# BFmsp430.net
KiCad netlist of a schematic drawn in Altium Designer
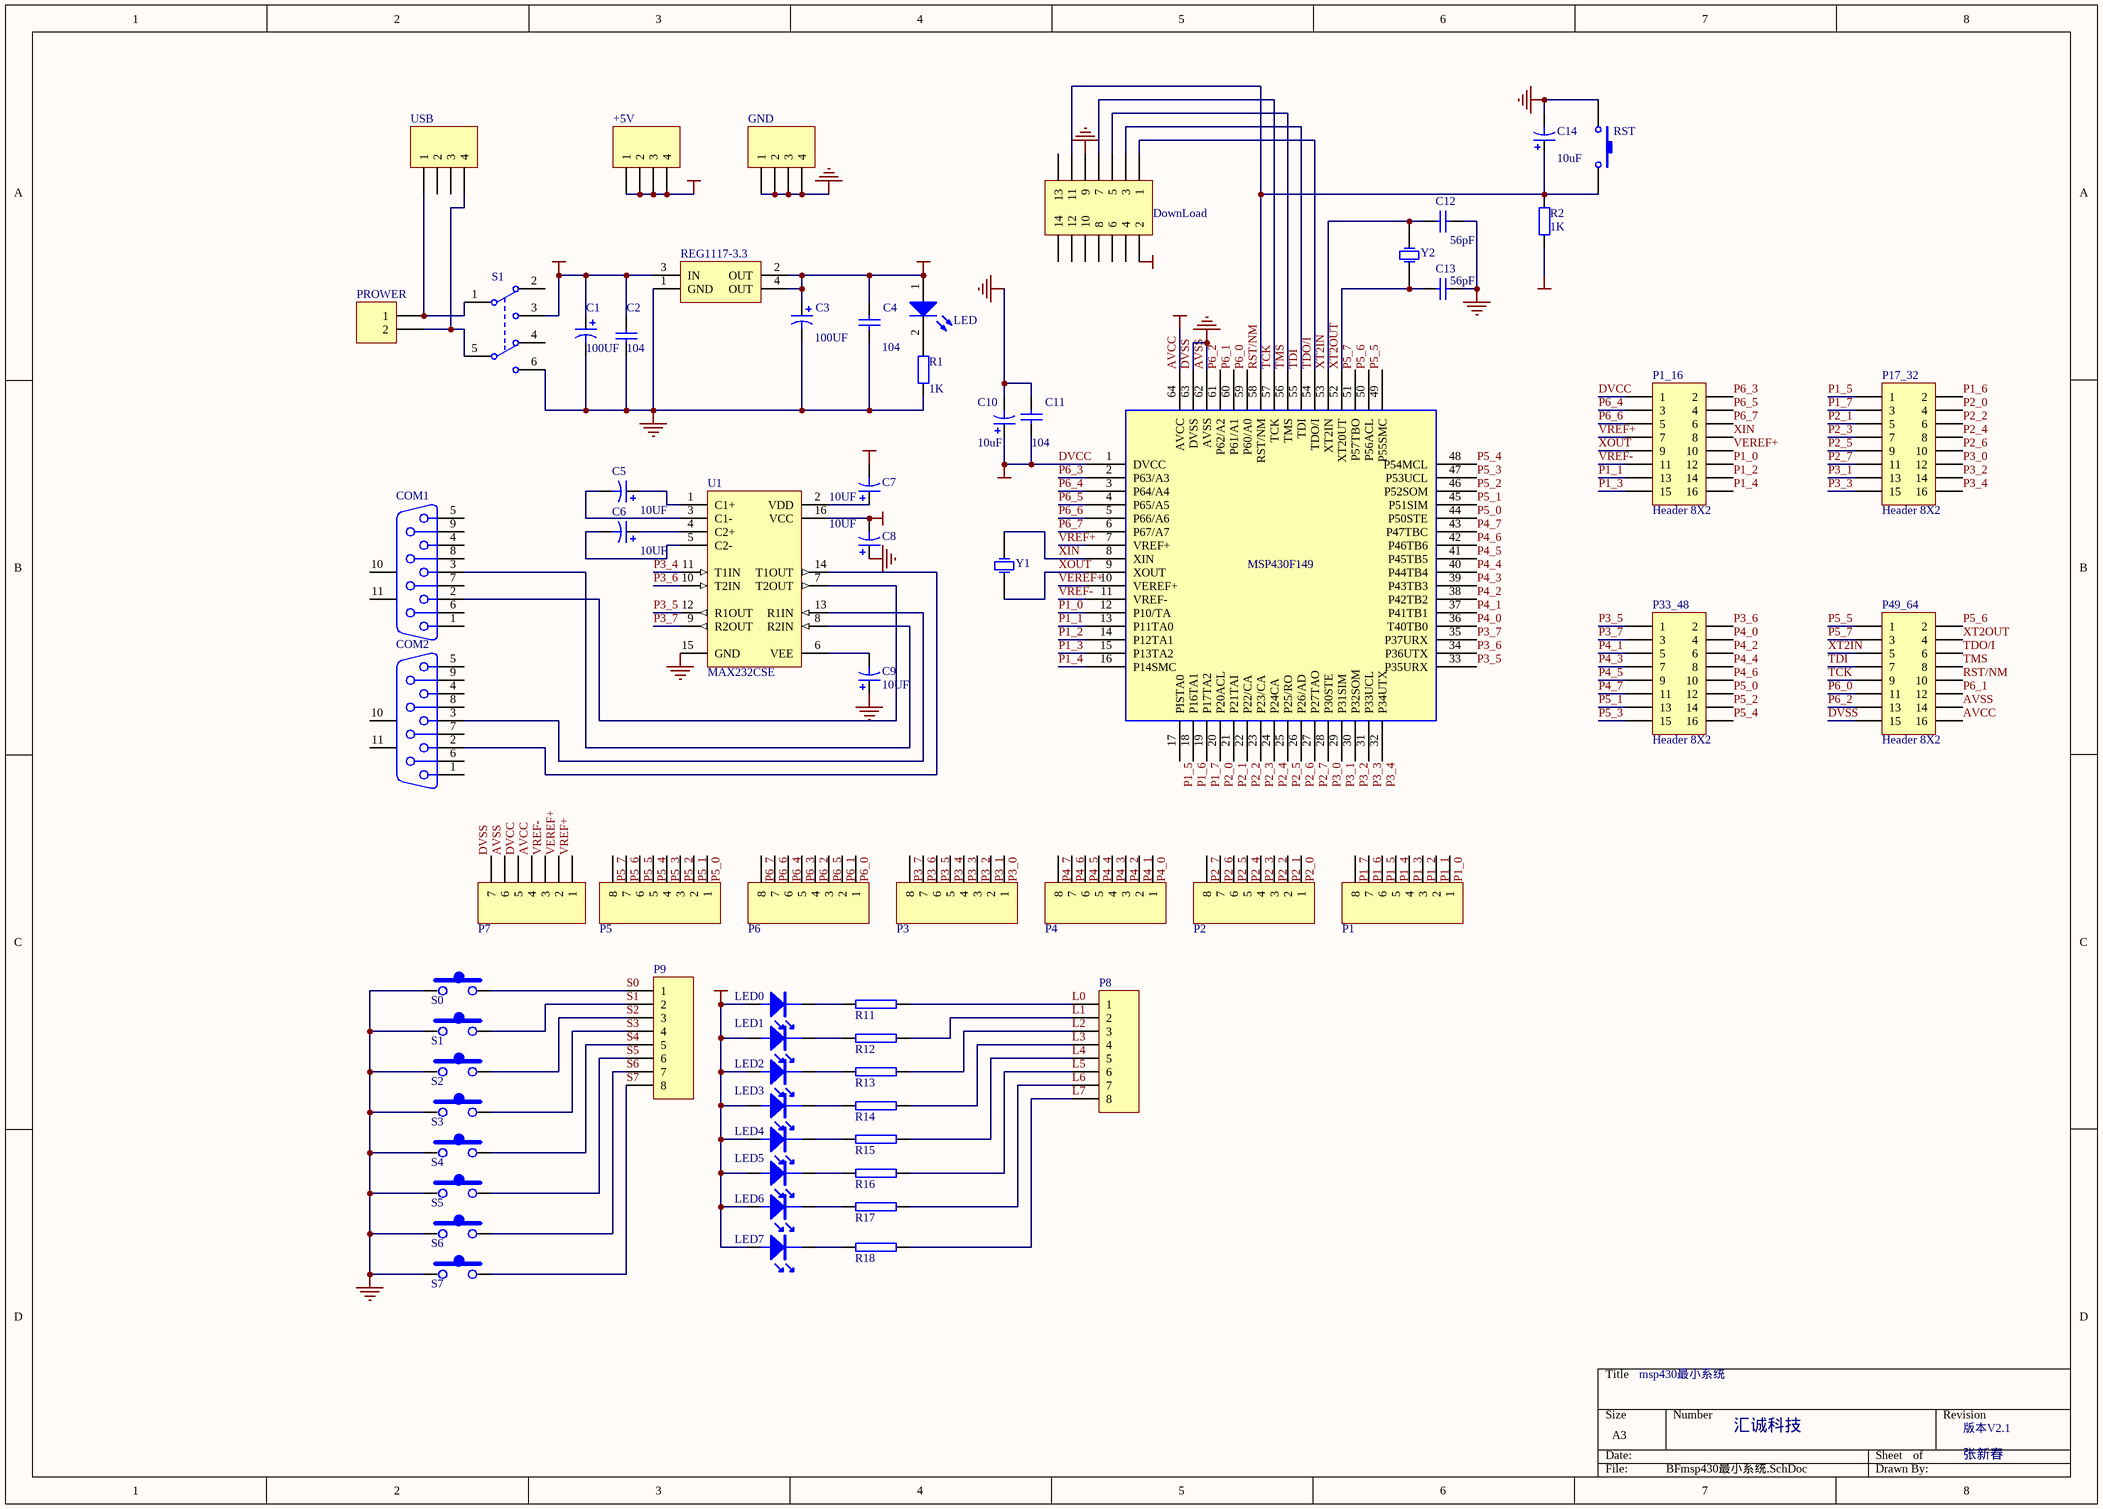
[diagram p0: BFmsp430最小系统.SchDoc]

(export (version "E")
  (design (tool "Eeschema 10.0.6"))
  (components
    (comp (ref "+5V")
      (value "Header 4")
      (footprint "HDR1X4")
      (description "Header, 4-Pin")
      (fields (field (name "PUBLISHER") "Altium Limited"))
      (libsource (lib "Miscellaneous Connectors") (part "Header 4"))
    )
    (comp (ref "1") (value "S0") (footprint "an-6*6") (libsource (lib "OldCow1 (1)") (part "KEY")))
    (comp (ref "2") (value "S1") (footprint "an-6*6") (libsource (lib "OldCow1 (1)") (part "KEY")))
    (comp (ref "3") (value "S2") (footprint "an-6*6") (libsource (lib "OldCow1 (1)") (part "KEY")))
    (comp (ref "4") (value "S3") (footprint "an-6*6") (libsource (lib "OldCow1 (1)") (part "KEY")))
    (comp (ref "5") (value "S4") (footprint "an-6*6") (libsource (lib "OldCow1 (1)") (part "KEY")))
    (comp (ref "6") (value "S5") (footprint "an-6*6") (libsource (lib "OldCow1 (1)") (part "KEY")))
    (comp (ref "7") (value "S6") (footprint "an-6*6") (libsource (lib "OldCow1 (1)") (part "KEY")))
    (comp (ref "8") (value "S7") (footprint "an-6*6") (libsource (lib "OldCow1 (1)") (part "KEY")))
    (comp (ref "C1")
      (value "100UF")
      (footprint "C-DJ-6")
      (description "Polarized Capacitor (Radial)")
      (fields (field (name "Comment") "Cap Pol1") (field (name "PUBLISHER") "Altium Limited"))
      (libsource (lib "Miscellaneous Devices") (part "Cap Pol1"))
    )
    (comp (ref "C2")
      (value "104")
      (footprint "CPDR")
      (description "Capacitor (Semiconductor SIM Model)")
      (fields (field (name "Comment") "Cap Semi") (field (name "PUBLISHER") "Altium Limited"))
      (libsource (lib "Miscellaneous Devices") (part "Cap Semi"))
    )
    (comp (ref "C3")
      (value "100UF")
      (footprint "C-DJ-4")
      (description "Polarized Capacitor (Radial)")
      (fields (field (name "Comment") "Cap Pol1") (field (name "PUBLISHER") "Altium Limited"))
      (libsource (lib "Miscellaneous Devices") (part "Cap Pol1"))
    )
    (comp (ref "C4")
      (value "104")
      (footprint "CPDR")
      (description "Capacitor (Semiconductor SIM Model)")
      (fields (field (name "Comment") "Cap Semi") (field (name "PUBLISHER") "Altium Limited"))
      (libsource (lib "Miscellaneous Devices") (part "Cap Semi"))
    )
    (comp (ref "C5")
      (value "10UF")
      (footprint "C-DJ-4")
      (description "Polarized Capacitor (Radial)")
      (fields (field (name "Comment") "Cap Pol1") (field (name "PUBLISHER") "Altium Limited"))
      (libsource (lib "Miscellaneous Devices") (part "Cap Pol1"))
    )
    (comp (ref "C6")
      (value "10UF")
      (footprint "C-DJ-4")
      (description "Polarized Capacitor (Radial)")
      (fields (field (name "Comment") "Cap Pol1") (field (name "PUBLISHER") "Altium Limited"))
      (libsource (lib "Miscellaneous Devices") (part "Cap Pol1"))
    )
    (comp (ref "C7")
      (value "10UF")
      (footprint "C-DJ-4")
      (description "Polarized Capacitor (Radial)")
      (fields (field (name "Comment") "Cap Pol1") (field (name "PUBLISHER") "Altium Limited"))
      (libsource (lib "Miscellaneous Devices") (part "Cap Pol1"))
    )
    (comp (ref "C8")
      (value "10UF")
      (footprint "C-DJ-4")
      (description "Polarized Capacitor (Radial)")
      (fields (field (name "Comment") "Cap Pol1") (field (name "PUBLISHER") "Altium Limited"))
      (libsource (lib "Miscellaneous Devices") (part "Cap Pol1"))
    )
    (comp (ref "C9")
      (value "10UF")
      (footprint "C-DJ-4")
      (description "Polarized Capacitor (Radial)")
      (fields (field (name "Comment") "Cap Pol1") (field (name "PUBLISHER") "Altium Limited"))
      (libsource (lib "Miscellaneous Devices") (part "Cap Pol1"))
    )
    (comp (ref "C10")
      (value "10uF")
      (footprint "C-DJ-4")
      (description "Polarized Capacitor (Radial)")
      (fields (field (name "Comment") "Cap Pol1") (field (name "PUBLISHER") "Altium Limited"))
      (libsource (lib "Miscellaneous Devices") (part "Cap Pol1"))
    )
    (comp (ref "C11")
      (value "104")
      (footprint "CPDR")
      (description "Capacitor (Semiconductor SIM Model)")
      (fields (field (name "Comment") "Cap Semi") (field (name "PUBLISHER") "Altium Limited"))
      (libsource (lib "Miscellaneous Devices") (part "Cap Semi"))
    )
    (comp (ref "C12")
      (value "56pF")
      (footprint "CPDR")
      (description "瓷片电容")
      (fields (field (name "Comment") "CPDR") (field (name "PUBLISHER") "Altium Limited"))
      (libsource (lib "zxcourhc") (part "CPDR"))
    )
    (comp (ref "C13")
      (value "56pF")
      (footprint "CPDR")
      (description "瓷片电容")
      (fields (field (name "Comment") "CPDR") (field (name "PUBLISHER") "Altium Limited"))
      (libsource (lib "zxcourhc") (part "CPDR"))
    )
    (comp (ref "C14")
      (value "10uF")
      (footprint "C-DJ-4")
      (description "Polarized Capacitor (Radial)")
      (fields (field (name "Comment") "Cap Pol1") (field (name "PUBLISHER") "Altium Limited"))
      (libsource (lib "Miscellaneous Devices") (part "Cap Pol1"))
    )
    (comp (ref "COM1")
      (value "D Connector 9")
      (footprint "zxcourhc:COM-9")
      (description "Receptacle Assembly, 9 Position, Right Angle")
      (fields (field (name "PUBLISHER") "Altium Limited"))
      (libsource (lib "Miscellaneous Connectors") (part "D Connector 9"))
    )
    (comp (ref "COM2")
      (value "D Connector 9")
      (footprint "zxcourhc:COM-9")
      (description "Receptacle Assembly, 9 Position, Right Angle")
      (fields (field (name "PUBLISHER") "Altium Limited"))
      (libsource (lib "Miscellaneous Connectors") (part "D Connector 9"))
    )
    (comp (ref "DownLoad")
      (value "Header 7X2")
      (footprint "HDR-2X7")
      (description "Header, 7-Pin, Dual row")
      (fields (field (name "PUBLISHER") "Altium Limited"))
      (libsource (lib "Miscellaneous Connectors") (part "Header 7X2"))
    )
    (comp (ref "DS1")
      (value "LED")
      (footprint "LED")
      (description "发光二极管")
      (fields (field (name "PUBLISHER") "Altium Limited"))
      (libsource (lib "zxcourhc") (part "LED"))
    )
    (comp (ref "GND")
      (value "Header 4")
      (footprint "HDR1X4")
      (description "Header, 4-Pin")
      (fields (field (name "PUBLISHER") "Altium Limited"))
      (libsource (lib "Miscellaneous Connectors") (part "Header 4"))
    )
    (comp (ref "LED0") (value "LED") (footprint "TP-0805-D") (libsource (lib "OldCow1 (1)") (part "LED")))
    (comp (ref "LED1") (value "LED") (footprint "TP-0805-D") (libsource (lib "OldCow1 (1)") (part "LED")))
    (comp (ref "LED2") (value "LED") (footprint "TP-0805-D") (libsource (lib "OldCow1 (1)") (part "LED")))
    (comp (ref "LED3") (value "LED") (footprint "TP-0805-D") (libsource (lib "OldCow1 (1)") (part "LED")))
    (comp (ref "LED4") (value "LED") (footprint "TP-0805-D") (libsource (lib "OldCow1 (1)") (part "LED")))
    (comp (ref "LED5") (value "LED") (footprint "TP-0805-D") (libsource (lib "OldCow1 (1)") (part "LED")))
    (comp (ref "LED6") (value "LED") (footprint "TP-0805-D") (libsource (lib "OldCow1 (1)") (part "LED")))
    (comp (ref "LED7") (value "LED") (footprint "TP-0805-D") (libsource (lib "OldCow1 (1)") (part "LED")))
    (comp (ref "MSP430F149")
      (value "MSP430F149")
      (footprint "MPS430149")
      (libsource (lib "MyInt_Lib") (part "MSP430F133"))
    )
    (comp (ref "P1")
      (value "Header 8")
      (footprint "zxcourhc:HDR-8")
      (description "Header, 8-Pin")
      (fields (field (name "PUBLISHER") "Altium Limited"))
      (libsource (lib "Miscellaneous Connectors") (part "Header 8"))
    )
    (comp (ref "P1_16")
      (value "Header 8X2")
      (footprint "HDR2X8")
      (description "Header, 8-Pin, Dual row")
      (fields (field (name "PUBLISHER") "Altium Limited"))
      (libsource (lib "Miscellaneous Connectors") (part "Header 8X2"))
    )
    (comp (ref "P2")
      (value "Header 8")
      (footprint "zxcourhc:HD-8")
      (description "Header, 8-Pin")
      (fields (field (name "PUBLISHER") "Altium Limited"))
      (libsource (lib "Miscellaneous Connectors") (part "Header 8"))
    )
    (comp (ref "P3")
      (value "Header 8")
      (footprint "zxcourhc:HD-8")
      (description "Header, 8-Pin")
      (fields (field (name "PUBLISHER") "Altium Limited"))
      (libsource (lib "Miscellaneous Connectors") (part "Header 8"))
    )
    (comp (ref "P4")
      (value "Header 8")
      (footprint "zxcourhc:HD-8")
      (description "Header, 8-Pin")
      (fields (field (name "PUBLISHER") "Altium Limited"))
      (libsource (lib "Miscellaneous Connectors") (part "Header 8"))
    )
    (comp (ref "P5")
      (value "Header 8")
      (footprint "zxcourhc:HD-8")
      (description "Header, 8-Pin")
      (fields (field (name "PUBLISHER") "Altium Limited"))
      (libsource (lib "Miscellaneous Connectors") (part "Header 8"))
    )
    (comp (ref "P6")
      (value "Header 8")
      (footprint "zxcourhc:HD-8")
      (description "Header, 8-Pin")
      (fields (field (name "PUBLISHER") "Altium Limited"))
      (libsource (lib "Miscellaneous Connectors") (part "Header 8"))
    )
    (comp (ref "P7")
      (value "Header 7")
      (footprint "HDR1X7")
      (description "Header, 7-Pin")
      (fields (field (name "PUBLISHER") "Altium Limited"))
      (libsource (lib "Miscellaneous Connectors") (part "Header 7"))
    )
    (comp (ref "P8")
      (value "PZ_8")
      (footprint "HDR-8")
      (description "排针——8")
      (fields (field (name "PUBLISHER") "Altium Limited"))
      (libsource (lib "zxcourhc") (part "PZ_8"))
    )
    (comp (ref "P9")
      (value "PZ_8")
      (footprint "HDR-8")
      (description "排针——8")
      (fields (field (name "PUBLISHER") "Altium Limited"))
      (libsource (lib "zxcourhc") (part "PZ_8"))
    )
    (comp (ref "P17_32")
      (value "Header 8X2")
      (footprint "HDR2X8")
      (description "Header, 8-Pin, Dual row")
      (fields (field (name "PUBLISHER") "Altium Limited"))
      (libsource (lib "Miscellaneous Connectors") (part "Header 8X2"))
    )
    (comp (ref "P33_48")
      (value "Header 8X2")
      (footprint "HDR2X8")
      (description "Header, 8-Pin, Dual row")
      (fields (field (name "PUBLISHER") "Altium Limited"))
      (libsource (lib "Miscellaneous Connectors") (part "Header 8X2"))
    )
    (comp (ref "P49_64")
      (value "Header 8X2")
      (footprint "HDR2X8")
      (description "Header, 8-Pin, Dual row")
      (fields (field (name "PUBLISHER") "Altium Limited"))
      (libsource (lib "Miscellaneous Connectors") (part "Header 8X2"))
    )
    (comp (ref "PROWER")
      (value "PZ_2")
      (footprint "zxcourhc:JK128_2")
      (description "排针——2")
      (fields (field (name "PUBLISHER") "Altium Limited"))
      (libsource (lib "zxcourhc") (part "PZ_2"))
    )
    (comp (ref "R1")
      (value "1K")
      (footprint "TP-0805-R")
      (description "电阻")
      (fields (field (name "Comment") "Res") (field (name "PUBLISHER") "Altium Limited"))
      (libsource (lib "zxcourhc") (part "Res"))
    )
    (comp (ref "R2")
      (value "1K")
      (footprint "TP-0805-R")
      (description "电阻")
      (fields (field (name "Comment") "Res") (field (name "PUBLISHER") "Altium Limited"))
      (libsource (lib "zxcourhc") (part "Res"))
    )
    (comp (ref "R11") (value "RES1") (footprint "TP-0805-R") (libsource (lib "OldCow1 (1)") (part "RES1")))
    (comp (ref "R12") (value "RES1") (footprint "TP-0805-R") (libsource (lib "OldCow1 (1)") (part "RES1")))
    (comp (ref "R13") (value "RES1") (footprint "TP-0805-R") (libsource (lib "OldCow1 (1)") (part "RES1")))
    (comp (ref "R14") (value "RES1") (footprint "TP-0805-R") (libsource (lib "OldCow1 (1)") (part "RES1")))
    (comp (ref "R15") (value "RES1") (footprint "TP-0805-R") (libsource (lib "OldCow1 (1)") (part "RES1")))
    (comp (ref "R16") (value "RES1") (footprint "TP-0805-R") (libsource (lib "OldCow1 (1)") (part "RES1")))
    (comp (ref "R17") (value "RES1") (footprint "TP-0805-R") (libsource (lib "OldCow1 (1)") (part "RES1")))
    (comp (ref "R18") (value "RES1") (footprint "TP-0805-R") (libsource (lib "OldCow1 (1)") (part "RES1")))
    (comp (ref "REG1117-3.3")
      (value "REG1117-3.3")
      (footprint "ZZ311")
      (description "800mA and 1A Low Dropout Positive Regulator 2.85V, 3.3V, 5V, and Adjustable")
      (fields (field (name "PUBLISHER") "Altium Limited"))
      (libsource (lib "BB Power Mgt Voltage Regulator") (part "REG1117-3.3"))
    )
    (comp (ref "RST")
      (value "AJKG")
      (footprint "an-6*6")
      (description "按键开关")
      (fields (field (name "PUBLISHER") "Altium Limited"))
      (libsource (lib "zxcourhc") (part "AJKG"))
    )
    (comp (ref "S1")
      (value "ZSKG_KEY")
      (footprint "zxcourhc:DPDT-6")
      (description "自锁开关")
      (fields (field (name "PUBLISHER") "Altium Limited"))
      (libsource (lib "zxcourhc") (part "ZSKG_KEY"))
    )
    (comp (ref "U1")
      (value "MAX232CSE")
      (footprint "DIP-16")
      (description "+5V Powered, Multi-Channel RS-232 Driver/Receiver")
      (fields (field (name "PUBLISHER") "Altium Limited"))
      (libsource (lib "Maxim Communication Transceiver") (part "MAX232CSE"))
    )
    (comp (ref "USB")
      (value "PZ_4")
      (footprint "zxcourhc:USB-5V")
      (description "排针——4")
      (fields (field (name "PUBLISHER") "Altium Limited"))
      (libsource (lib "zxcourhc") (part "PZ_4"))
    )
    (comp (ref "Y1")
      (value "XTAL")
      (footprint "BCY-W2/D3.1")
      (description "Crystal Oscillator")
      (fields (field (name "PUBLISHER") "Altium Limited"))
      (libsource (lib "Miscellaneous Devices") (part "XTAL"))
    )
    (comp (ref "Y2")
      (value "XTAL")
      (footprint "JZ_ZC")
      (description "Crystal Oscillator")
      (fields (field (name "PUBLISHER") "Altium Limited"))
      (libsource (lib "Miscellaneous Devices") (part "XTAL"))
    )
  )
  (nets
    (net (code "1") (name "+5V") (class "Default")
      (node (ref "+5V") (pin "1") (pinfunction "1_1") (pintype "passive"))
      (node (ref "+5V") (pin "2") (pinfunction "2_2") (pintype "passive"))
      (node (ref "+5V") (pin "3") (pinfunction "3_3") (pintype "passive"))
      (node (ref "+5V") (pin "4") (pinfunction "4_4") (pintype "passive"))
      (node (ref "C1") (pin "1") (pinfunction "1_1") (pintype "passive"))
      (node (ref "C2") (pin "2") (pinfunction "2_2") (pintype "passive"))
      (node (ref "REG1117-3.3") (pin "3") (pinfunction "IN_3") (pintype "power_in"))
      (node (ref "S1") (pin "3") (pinfunction "NO1_3") (pintype "passive"))
    )
    (net (code "2") (name "/L0") (class "Default")
      (node (ref "P8") (pin "1") (pinfunction "1_1") (pintype "passive"))
      (node (ref "R11") (pin "1") (pinfunction "1_1") (pintype "passive"))
    )
    (net (code "3") (name "/L1") (class "Default")
      (node (ref "P8") (pin "2") (pinfunction "2_2") (pintype "passive"))
      (node (ref "R12") (pin "1") (pinfunction "1_1") (pintype "passive"))
    )
    (net (code "4") (name "/L2") (class "Default")
      (node (ref "P8") (pin "3") (pinfunction "3_3") (pintype "passive"))
      (node (ref "R13") (pin "1") (pinfunction "1_1") (pintype "passive"))
    )
    (net (code "5") (name "/L3") (class "Default")
      (node (ref "P8") (pin "4") (pinfunction "4_4") (pintype "passive"))
      (node (ref "R14") (pin "1") (pinfunction "1_1") (pintype "passive"))
    )
    (net (code "6") (name "/L4") (class "Default")
      (node (ref "P8") (pin "5") (pinfunction "5_5") (pintype "passive"))
      (node (ref "R15") (pin "1") (pinfunction "1_1") (pintype "passive"))
    )
    (net (code "7") (name "/L5") (class "Default")
      (node (ref "P8") (pin "6") (pinfunction "6_6") (pintype "passive"))
      (node (ref "R16") (pin "1") (pinfunction "1_1") (pintype "passive"))
    )
    (net (code "8") (name "/L6") (class "Default")
      (node (ref "P8") (pin "7") (pinfunction "7_7") (pintype "passive"))
      (node (ref "R17") (pin "1") (pinfunction "1_1") (pintype "passive"))
    )
    (net (code "9") (name "/L7") (class "Default")
      (node (ref "P8") (pin "8") (pinfunction "8_8") (pintype "passive"))
      (node (ref "R18") (pin "1") (pinfunction "1_1") (pintype "passive"))
    )
    (net (code "10") (name "/P1_0") (class "Default")
      (node (ref "MSP430F149") (pin "12") (pinfunction "P10/TA_12") (pintype "passive"))
      (node (ref "P1") (pin "1") (pinfunction "1_1") (pintype "passive"))
      (node (ref "P1_16") (pin "12") (pinfunction "12_12") (pintype "passive"))
    )
    (net (code "11") (name "/P1_1") (class "Default")
      (node (ref "MSP430F149") (pin "13") (pinfunction "P11TA0_13") (pintype "passive"))
      (node (ref "P1") (pin "2") (pinfunction "2_2") (pintype "passive"))
      (node (ref "P1_16") (pin "13") (pinfunction "13_13") (pintype "passive"))
    )
    (net (code "12") (name "/P1_2") (class "Default")
      (node (ref "MSP430F149") (pin "14") (pinfunction "P12TA1_14") (pintype "passive"))
      (node (ref "P1") (pin "3") (pinfunction "3_3") (pintype "passive"))
      (node (ref "P1_16") (pin "14") (pinfunction "14_14") (pintype "passive"))
    )
    (net (code "13") (name "/P1_3") (class "Default")
      (node (ref "MSP430F149") (pin "15") (pinfunction "P13TA2_15") (pintype "passive"))
      (node (ref "P1") (pin "4") (pinfunction "4_4") (pintype "passive"))
      (node (ref "P1_16") (pin "15") (pinfunction "15_15") (pintype "passive"))
    )
    (net (code "14") (name "/P1_4") (class "Default")
      (node (ref "MSP430F149") (pin "16") (pinfunction "P14SMC_16") (pintype "passive"))
      (node (ref "P1") (pin "5") (pinfunction "5_5") (pintype "passive"))
      (node (ref "P1_16") (pin "16") (pinfunction "16_16") (pintype "passive"))
    )
    (net (code "15") (name "/P1_5") (class "Default")
      (node (ref "MSP430F149") (pin "17") (pinfunction "PISTA0_17") (pintype "passive"))
      (node (ref "P1") (pin "6") (pinfunction "6_6") (pintype "passive"))
      (node (ref "P17_32") (pin "1") (pinfunction "1_1") (pintype "passive"))
    )
    (net (code "16") (name "/P1_6") (class "Default")
      (node (ref "MSP430F149") (pin "18") (pinfunction "P16TA1_18") (pintype "passive"))
      (node (ref "P1") (pin "7") (pinfunction "7_7") (pintype "passive"))
      (node (ref "P17_32") (pin "2") (pinfunction "2_2") (pintype "passive"))
    )
    (net (code "17") (name "/P1_7") (class "Default")
      (node (ref "MSP430F149") (pin "19") (pinfunction "P17TA2_19") (pintype "passive"))
      (node (ref "P1") (pin "8") (pinfunction "8_8") (pintype "passive"))
      (node (ref "P17_32") (pin "3") (pinfunction "3_3") (pintype "passive"))
    )
    (net (code "18") (name "/P2_0") (class "Default")
      (node (ref "MSP430F149") (pin "20") (pinfunction "P20ACL_20") (pintype "passive"))
      (node (ref "P17_32") (pin "4") (pinfunction "4_4") (pintype "passive"))
      (node (ref "P2") (pin "1") (pinfunction "1_1") (pintype "passive"))
    )
    (net (code "19") (name "/P2_1") (class "Default")
      (node (ref "MSP430F149") (pin "21") (pinfunction "P21TAI_21") (pintype "passive"))
      (node (ref "P17_32") (pin "5") (pinfunction "5_5") (pintype "passive"))
      (node (ref "P2") (pin "2") (pinfunction "2_2") (pintype "passive"))
    )
    (net (code "20") (name "/P2_2") (class "Default")
      (node (ref "MSP430F149") (pin "22") (pinfunction "P22/CA_22") (pintype "passive"))
      (node (ref "P17_32") (pin "6") (pinfunction "6_6") (pintype "passive"))
      (node (ref "P2") (pin "3") (pinfunction "3_3") (pintype "passive"))
    )
    (net (code "21") (name "/P2_3") (class "Default")
      (node (ref "MSP430F149") (pin "23") (pinfunction "P23/CA_23") (pintype "passive"))
      (node (ref "P17_32") (pin "7") (pinfunction "7_7") (pintype "passive"))
      (node (ref "P2") (pin "4") (pinfunction "4_4") (pintype "passive"))
    )
    (net (code "22") (name "/P2_4") (class "Default")
      (node (ref "MSP430F149") (pin "24") (pinfunction "P24CA_24") (pintype "passive"))
      (node (ref "P17_32") (pin "8") (pinfunction "8_8") (pintype "passive"))
      (node (ref "P2") (pin "5") (pinfunction "5_5") (pintype "passive"))
    )
    (net (code "23") (name "/P2_5") (class "Default")
      (node (ref "MSP430F149") (pin "25") (pinfunction "P25/RO_25") (pintype "passive"))
      (node (ref "P17_32") (pin "9") (pinfunction "9_9") (pintype "passive"))
      (node (ref "P2") (pin "6") (pinfunction "6_6") (pintype "passive"))
    )
    (net (code "24") (name "/P2_6") (class "Default")
      (node (ref "MSP430F149") (pin "26") (pinfunction "P26/AD_26") (pintype "passive"))
      (node (ref "P17_32") (pin "10") (pinfunction "10_10") (pintype "passive"))
      (node (ref "P2") (pin "7") (pinfunction "7_7") (pintype "passive"))
    )
    (net (code "25") (name "/P2_7") (class "Default")
      (node (ref "MSP430F149") (pin "27") (pinfunction "P27TAO_27") (pintype "passive"))
      (node (ref "P17_32") (pin "11") (pinfunction "11_11") (pintype "passive"))
      (node (ref "P2") (pin "8") (pinfunction "8_8") (pintype "passive"))
    )
    (net (code "26") (name "/P3_0") (class "Default")
      (node (ref "MSP430F149") (pin "28") (pinfunction "P30STE_28") (pintype "passive"))
      (node (ref "P17_32") (pin "12") (pinfunction "12_12") (pintype "passive"))
      (node (ref "P3") (pin "1") (pinfunction "1_1") (pintype "passive"))
    )
    (net (code "27") (name "/P3_1") (class "Default")
      (node (ref "MSP430F149") (pin "29") (pinfunction "P31SIM_29") (pintype "passive"))
      (node (ref "P17_32") (pin "13") (pinfunction "13_13") (pintype "passive"))
      (node (ref "P3") (pin "2") (pinfunction "2_2") (pintype "passive"))
    )
    (net (code "28") (name "/P3_2") (class "Default")
      (node (ref "MSP430F149") (pin "30") (pinfunction "P32SOM_30") (pintype "passive"))
      (node (ref "P17_32") (pin "14") (pinfunction "14_14") (pintype "passive"))
      (node (ref "P3") (pin "3") (pinfunction "3_3") (pintype "passive"))
    )
    (net (code "29") (name "/P3_3") (class "Default")
      (node (ref "MSP430F149") (pin "31") (pinfunction "P33UCL_31") (pintype "passive"))
      (node (ref "P17_32") (pin "15") (pinfunction "15_15") (pintype "passive"))
      (node (ref "P3") (pin "4") (pinfunction "4_4") (pintype "passive"))
    )
    (net (code "30") (name "/P3_4") (class "Default")
      (node (ref "MSP430F149") (pin "32") (pinfunction "P34UTX_32") (pintype "passive"))
      (node (ref "P17_32") (pin "16") (pinfunction "16_16") (pintype "passive"))
      (node (ref "P3") (pin "5") (pinfunction "5_5") (pintype "passive"))
      (node (ref "U1") (pin "11") (pinfunction "T1IN_11") (pintype "input"))
    )
    (net (code "31") (name "/P3_5") (class "Default")
      (node (ref "MSP430F149") (pin "33") (pinfunction "P35URX_33") (pintype "passive"))
      (node (ref "P3") (pin "6") (pinfunction "6_6") (pintype "passive"))
      (node (ref "P33_48") (pin "1") (pinfunction "1_1") (pintype "passive"))
      (node (ref "U1") (pin "12") (pinfunction "R1OUT_12") (pintype "output"))
    )
    (net (code "32") (name "/P3_6") (class "Default")
      (node (ref "MSP430F149") (pin "34") (pinfunction "P36UTX_34") (pintype "passive"))
      (node (ref "P3") (pin "7") (pinfunction "7_7") (pintype "passive"))
      (node (ref "P33_48") (pin "2") (pinfunction "2_2") (pintype "passive"))
      (node (ref "U1") (pin "10") (pinfunction "T2IN_10") (pintype "input"))
    )
    (net (code "33") (name "/P3_7") (class "Default")
      (node (ref "MSP430F149") (pin "35") (pinfunction "P37URX_35") (pintype "passive"))
      (node (ref "P3") (pin "8") (pinfunction "8_8") (pintype "passive"))
      (node (ref "P33_48") (pin "3") (pinfunction "3_3") (pintype "passive"))
      (node (ref "U1") (pin "9") (pinfunction "R2OUT_9") (pintype "output"))
    )
    (net (code "34") (name "/P4_0") (class "Default")
      (node (ref "MSP430F149") (pin "36") (pinfunction "T40TB0_36") (pintype "passive"))
      (node (ref "P33_48") (pin "4") (pinfunction "4_4") (pintype "passive"))
      (node (ref "P4") (pin "1") (pinfunction "1_1") (pintype "passive"))
    )
    (net (code "35") (name "/P4_1") (class "Default")
      (node (ref "MSP430F149") (pin "37") (pinfunction "P41TB1_37") (pintype "passive"))
      (node (ref "P33_48") (pin "5") (pinfunction "5_5") (pintype "passive"))
      (node (ref "P4") (pin "2") (pinfunction "2_2") (pintype "passive"))
    )
    (net (code "36") (name "/P4_2") (class "Default")
      (node (ref "MSP430F149") (pin "38") (pinfunction "P42TB2_38") (pintype "passive"))
      (node (ref "P33_48") (pin "6") (pinfunction "6_6") (pintype "passive"))
      (node (ref "P4") (pin "3") (pinfunction "3_3") (pintype "passive"))
    )
    (net (code "37") (name "/P4_3") (class "Default")
      (node (ref "MSP430F149") (pin "39") (pinfunction "P43TB3_39") (pintype "passive"))
      (node (ref "P33_48") (pin "7") (pinfunction "7_7") (pintype "passive"))
      (node (ref "P4") (pin "4") (pinfunction "4_4") (pintype "passive"))
    )
    (net (code "38") (name "/P4_4") (class "Default")
      (node (ref "MSP430F149") (pin "40") (pinfunction "P44TB4_40") (pintype "passive"))
      (node (ref "P33_48") (pin "8") (pinfunction "8_8") (pintype "passive"))
      (node (ref "P4") (pin "5") (pinfunction "5_5") (pintype "passive"))
    )
    (net (code "39") (name "/P4_5") (class "Default")
      (node (ref "MSP430F149") (pin "41") (pinfunction "P45TB5_41") (pintype "passive"))
      (node (ref "P33_48") (pin "9") (pinfunction "9_9") (pintype "passive"))
      (node (ref "P4") (pin "6") (pinfunction "6_6") (pintype "passive"))
    )
    (net (code "40") (name "/P4_6") (class "Default")
      (node (ref "MSP430F149") (pin "42") (pinfunction "P46TB6_42") (pintype "passive"))
      (node (ref "P33_48") (pin "10") (pinfunction "10_10") (pintype "passive"))
      (node (ref "P4") (pin "7") (pinfunction "7_7") (pintype "passive"))
    )
    (net (code "41") (name "/P4_7") (class "Default")
      (node (ref "MSP430F149") (pin "43") (pinfunction "P47TBC_43") (pintype "passive"))
      (node (ref "P33_48") (pin "11") (pinfunction "11_11") (pintype "passive"))
      (node (ref "P4") (pin "8") (pinfunction "8_8") (pintype "passive"))
    )
    (net (code "42") (name "/P5_0") (class "Default")
      (node (ref "MSP430F149") (pin "44") (pinfunction "P50STE_44") (pintype "passive"))
      (node (ref "P33_48") (pin "12") (pinfunction "12_12") (pintype "passive"))
      (node (ref "P5") (pin "1") (pinfunction "1_1") (pintype "passive"))
    )
    (net (code "43") (name "/P5_1") (class "Default")
      (node (ref "MSP430F149") (pin "45") (pinfunction "P51SIM_45") (pintype "passive"))
      (node (ref "P33_48") (pin "13") (pinfunction "13_13") (pintype "passive"))
      (node (ref "P5") (pin "2") (pinfunction "2_2") (pintype "passive"))
    )
    (net (code "44") (name "/P5_2") (class "Default")
      (node (ref "MSP430F149") (pin "46") (pinfunction "P52SOM_46") (pintype "passive"))
      (node (ref "P33_48") (pin "14") (pinfunction "14_14") (pintype "passive"))
      (node (ref "P5") (pin "3") (pinfunction "3_3") (pintype "passive"))
    )
    (net (code "45") (name "/P5_3") (class "Default")
      (node (ref "MSP430F149") (pin "47") (pinfunction "P53UCL_47") (pintype "passive"))
      (node (ref "P33_48") (pin "15") (pinfunction "15_15") (pintype "passive"))
      (node (ref "P5") (pin "4") (pinfunction "4_4") (pintype "passive"))
    )
    (net (code "46") (name "/P5_4") (class "Default")
      (node (ref "MSP430F149") (pin "48") (pinfunction "P54MCL_48") (pintype "passive"))
      (node (ref "P33_48") (pin "16") (pinfunction "16_16") (pintype "passive"))
      (node (ref "P5") (pin "5") (pinfunction "5_5") (pintype "passive"))
    )
    (net (code "47") (name "/P5_5") (class "Default")
      (node (ref "MSP430F149") (pin "49") (pinfunction "P55SMC_49") (pintype "passive"))
      (node (ref "P49_64") (pin "1") (pinfunction "1_1") (pintype "passive"))
      (node (ref "P5") (pin "6") (pinfunction "6_6") (pintype "passive"))
    )
    (net (code "48") (name "/P5_6") (class "Default")
      (node (ref "MSP430F149") (pin "50") (pinfunction "P56ACL_50") (pintype "passive"))
      (node (ref "P49_64") (pin "2") (pinfunction "2_2") (pintype "passive"))
      (node (ref "P5") (pin "7") (pinfunction "7_7") (pintype "passive"))
    )
    (net (code "49") (name "/P5_7") (class "Default")
      (node (ref "MSP430F149") (pin "51") (pinfunction "P57TBO_51") (pintype "passive"))
      (node (ref "P49_64") (pin "3") (pinfunction "3_3") (pintype "passive"))
      (node (ref "P5") (pin "8") (pinfunction "8_8") (pintype "passive"))
    )
    (net (code "50") (name "/P6_0") (class "Default")
      (node (ref "MSP430F149") (pin "59") (pinfunction "P60/A0_59") (pintype "passive"))
      (node (ref "P49_64") (pin "11") (pinfunction "11_11") (pintype "passive"))
      (node (ref "P6") (pin "1") (pinfunction "1_1") (pintype "passive"))
    )
    (net (code "51") (name "/P6_1") (class "Default")
      (node (ref "MSP430F149") (pin "60") (pinfunction "P61/A1_60") (pintype "passive"))
      (node (ref "P49_64") (pin "12") (pinfunction "12_12") (pintype "passive"))
      (node (ref "P6") (pin "2") (pinfunction "2_2") (pintype "passive"))
    )
    (net (code "52") (name "/P6_2") (class "Default")
      (node (ref "MSP430F149") (pin "61") (pinfunction "P62/A2_61") (pintype "passive"))
      (node (ref "P49_64") (pin "13") (pinfunction "13_13") (pintype "passive"))
      (node (ref "P6") (pin "4") (pinfunction "4_4") (pintype "passive"))
    )
    (net (code "53") (name "/P6_3") (class "Default")
      (node (ref "MSP430F149") (pin "2") (pinfunction "P63/A3_2") (pintype "passive"))
      (node (ref "P1_16") (pin "2") (pinfunction "2_2") (pintype "passive"))
      (node (ref "P6") (pin "5") (pinfunction "5_5") (pintype "passive"))
    )
    (net (code "54") (name "/P6_4") (class "Default")
      (node (ref "MSP430F149") (pin "3") (pinfunction "P64/A4_3") (pintype "passive"))
      (node (ref "P1_16") (pin "3") (pinfunction "3_3") (pintype "passive"))
      (node (ref "P6") (pin "6") (pinfunction "6_6") (pintype "passive"))
    )
    (net (code "55") (name "/P6_5") (class "Default")
      (node (ref "MSP430F149") (pin "4") (pinfunction "P65/A5_4") (pintype "passive"))
      (node (ref "P1_16") (pin "4") (pinfunction "4_4") (pintype "passive"))
      (node (ref "P6") (pin "3") (pinfunction "3_3") (pintype "passive"))
    )
    (net (code "56") (name "/P6_6") (class "Default")
      (node (ref "MSP430F149") (pin "5") (pinfunction "P66/A6_5") (pintype "passive"))
      (node (ref "P1_16") (pin "5") (pinfunction "5_5") (pintype "passive"))
      (node (ref "P6") (pin "7") (pinfunction "7_7") (pintype "passive"))
    )
    (net (code "57") (name "/P6_7") (class "Default")
      (node (ref "MSP430F149") (pin "6") (pinfunction "P67/A7_6") (pintype "passive"))
      (node (ref "P1_16") (pin "6") (pinfunction "6_6") (pintype "passive"))
      (node (ref "P6") (pin "8") (pinfunction "8_8") (pintype "passive"))
    )
    (net (code "58") (name "/RST{slash}NM") (class "Default")
      (node (ref "C14") (pin "1") (pinfunction "1_1") (pintype "passive"))
      (node (ref "DownLoad") (pin "11") (pinfunction "11_11") (pintype "passive"))
      (node (ref "MSP430F149") (pin "58") (pinfunction "RST/NM_58") (pintype "passive"))
      (node (ref "P49_64") (pin "10") (pinfunction "10_10") (pintype "passive"))
      (node (ref "R2") (pin "2") (pinfunction "2_2") (pintype "passive"))
      (node (ref "RST") (pin "2") (pinfunction "2_2") (pintype "passive"))
    )
    (net (code "59") (name "/S0") (class "Default")
      (node (ref "1") (pin "2") (pinfunction "2_2") (pintype "passive"))
      (node (ref "P9") (pin "1") (pinfunction "1_1") (pintype "passive"))
    )
    (net (code "60") (name "/S1") (class "Default")
      (node (ref "2") (pin "2") (pinfunction "2_2") (pintype "passive"))
      (node (ref "P9") (pin "2") (pinfunction "2_2") (pintype "passive"))
    )
    (net (code "61") (name "/S2") (class "Default")
      (node (ref "3") (pin "2") (pinfunction "2_2") (pintype "passive"))
      (node (ref "P9") (pin "3") (pinfunction "3_3") (pintype "passive"))
    )
    (net (code "62") (name "/S3") (class "Default")
      (node (ref "4") (pin "2") (pinfunction "2_2") (pintype "passive"))
      (node (ref "P9") (pin "4") (pinfunction "4_4") (pintype "passive"))
    )
    (net (code "63") (name "/S4") (class "Default")
      (node (ref "5") (pin "2") (pinfunction "2_2") (pintype "passive"))
      (node (ref "P9") (pin "5") (pinfunction "5_5") (pintype "passive"))
    )
    (net (code "64") (name "/S5") (class "Default")
      (node (ref "6") (pin "2") (pinfunction "2_2") (pintype "passive"))
      (node (ref "P9") (pin "6") (pinfunction "6_6") (pintype "passive"))
    )
    (net (code "65") (name "/S6") (class "Default")
      (node (ref "7") (pin "2") (pinfunction "2_2") (pintype "passive"))
      (node (ref "P9") (pin "7") (pinfunction "7_7") (pintype "passive"))
    )
    (net (code "66") (name "/S7") (class "Default")
      (node (ref "8") (pin "2") (pinfunction "2_2") (pintype "passive"))
      (node (ref "P9") (pin "8") (pinfunction "8_8") (pintype "passive"))
    )
    (net (code "67") (name "/TCK") (class "Default")
      (node (ref "DownLoad") (pin "7") (pinfunction "7_7") (pintype "passive"))
      (node (ref "MSP430F149") (pin "57") (pinfunction "TCK_57") (pintype "passive"))
      (node (ref "P49_64") (pin "9") (pinfunction "9_9") (pintype "passive"))
    )
    (net (code "68") (name "/TDI") (class "Default")
      (node (ref "DownLoad") (pin "3") (pinfunction "3_3") (pintype "passive"))
      (node (ref "MSP430F149") (pin "55") (pinfunction "TDI_55") (pintype "passive"))
      (node (ref "P49_64") (pin "7") (pinfunction "7_7") (pintype "passive"))
    )
    (net (code "69") (name "/TDO{slash}I") (class "Default")
      (node (ref "DownLoad") (pin "1") (pinfunction "1_1") (pintype "passive"))
      (node (ref "MSP430F149") (pin "54") (pinfunction "TDO/I_54") (pintype "passive"))
      (node (ref "P49_64") (pin "6") (pinfunction "6_6") (pintype "passive"))
    )
    (net (code "70") (name "/TMS") (class "Default")
      (node (ref "DownLoad") (pin "5") (pinfunction "5_5") (pintype "passive"))
      (node (ref "MSP430F149") (pin "56") (pinfunction "TMS_56") (pintype "passive"))
      (node (ref "P49_64") (pin "8") (pinfunction "8_8") (pintype "passive"))
    )
    (net (code "71") (name "/VEREF+") (class "Default")
      (node (ref "MSP430F149") (pin "10") (pinfunction "VEREF+_10") (pintype "passive"))
      (node (ref "P1_16") (pin "10") (pinfunction "10_10") (pintype "passive"))
      (node (ref "P7") (pin "2") (pinfunction "2_2") (pintype "passive"))
    )
    (net (code "72") (name "/VREF+") (class "Default")
      (node (ref "MSP430F149") (pin "7") (pinfunction "VREF+_7") (pintype "passive"))
      (node (ref "P1_16") (pin "7") (pinfunction "7_7") (pintype "passive"))
      (node (ref "P7") (pin "1") (pinfunction "1_1") (pintype "passive"))
    )
    (net (code "73") (name "/VREF-") (class "Default")
      (node (ref "MSP430F149") (pin "11") (pinfunction "VREF-_11") (pintype "passive"))
      (node (ref "P1_16") (pin "11") (pinfunction "11_11") (pintype "passive"))
      (node (ref "P7") (pin "3") (pinfunction "3_3") (pintype "passive"))
    )
    (net (code "74") (name "/XIN") (class "Default")
      (node (ref "MSP430F149") (pin "8") (pinfunction "XIN_8") (pintype "passive"))
      (node (ref "P1_16") (pin "8") (pinfunction "8_8") (pintype "passive"))
      (node (ref "Y1") (pin "1") (pinfunction "OSC1_1") (pintype "passive"))
    )
    (net (code "75") (name "/XOUT") (class "Default")
      (node (ref "MSP430F149") (pin "9") (pinfunction "XOUT_9") (pintype "passive"))
      (node (ref "P1_16") (pin "9") (pinfunction "9_9") (pintype "passive"))
      (node (ref "Y1") (pin "2") (pinfunction "OSC2_2") (pintype "passive"))
    )
    (net (code "76") (name "/XT2IN") (class "Default")
      (node (ref "C12") (pin "1") (pinfunction "1_1") (pintype "passive"))
      (node (ref "MSP430F149") (pin "53") (pinfunction "XT2IN_53") (pintype "passive"))
      (node (ref "P49_64") (pin "5") (pinfunction "5_5") (pintype "passive"))
      (node (ref "Y2") (pin "2") (pinfunction "OSC2_2") (pintype "passive"))
    )
    (net (code "77") (name "/XT2OUT") (class "Default")
      (node (ref "C13") (pin "1") (pinfunction "1_1") (pintype "passive"))
      (node (ref "MSP430F149") (pin "52") (pinfunction "XT20UT_52") (pintype "passive"))
      (node (ref "P49_64") (pin "4") (pinfunction "4_4") (pintype "passive"))
      (node (ref "Y2") (pin "1") (pinfunction "OSC1_1") (pintype "passive"))
    )
    (net (code "78") (name "5V") (class "Default")
      (node (ref "C7") (pin "2") (pinfunction "2_2") (pintype "passive"))
      (node (ref "C8") (pin "2") (pinfunction "2_2") (pintype "passive"))
      (node (ref "U1") (pin "16") (pinfunction "VCC_16") (pintype "power_in"))
    )
    (net (code "79") (name "GND") (class "Default")
      (node (ref "1") (pin "1") (pinfunction "1_1") (pintype "passive"))
      (node (ref "2") (pin "1") (pinfunction "1_1") (pintype "passive"))
      (node (ref "3") (pin "1") (pinfunction "1_1") (pintype "passive"))
      (node (ref "4") (pin "1") (pinfunction "1_1") (pintype "passive"))
      (node (ref "5") (pin "1") (pinfunction "1_1") (pintype "passive"))
      (node (ref "6") (pin "1") (pinfunction "1_1") (pintype "passive"))
      (node (ref "7") (pin "1") (pinfunction "1_1") (pintype "passive"))
      (node (ref "8") (pin "1") (pinfunction "1_1") (pintype "passive"))
      (node (ref "C1") (pin "2") (pinfunction "2_2") (pintype "passive"))
      (node (ref "C10") (pin "2") (pinfunction "2_2") (pintype "passive"))
      (node (ref "C11") (pin "2") (pinfunction "2_2") (pintype "passive"))
      (node (ref "C12") (pin "2") (pinfunction "2_2") (pintype "passive"))
      (node (ref "C13") (pin "2") (pinfunction "2_2") (pintype "passive"))
      (node (ref "C14") (pin "2") (pinfunction "2_2") (pintype "passive"))
      (node (ref "C2") (pin "1") (pinfunction "1_1") (pintype "passive"))
      (node (ref "C3") (pin "2") (pinfunction "2_2") (pintype "passive"))
      (node (ref "C4") (pin "1") (pinfunction "1_1") (pintype "passive"))
      (node (ref "C8") (pin "1") (pinfunction "1_1") (pintype "passive"))
      (node (ref "C9") (pin "1") (pinfunction "1_1") (pintype "passive"))
      (node (ref "DownLoad") (pin "9") (pinfunction "9_9") (pintype "passive"))
      (node (ref "GND") (pin "1") (pinfunction "1_1") (pintype "passive"))
      (node (ref "GND") (pin "2") (pinfunction "2_2") (pintype "passive"))
      (node (ref "GND") (pin "3") (pinfunction "3_3") (pintype "passive"))
      (node (ref "GND") (pin "4") (pinfunction "4_4") (pintype "passive"))
      (node (ref "MSP430F149") (pin "62") (pinfunction "AVSS_62") (pintype "passive"))
      (node (ref "MSP430F149") (pin "63") (pinfunction "DVSS_63") (pintype "passive"))
      (node (ref "P49_64") (pin "14") (pinfunction "14_14") (pintype "passive"))
      (node (ref "P49_64") (pin "15") (pinfunction "15_15") (pintype "passive"))
      (node (ref "P7") (pin "6") (pinfunction "6_6") (pintype "passive"))
      (node (ref "P7") (pin "7") (pinfunction "7_7") (pintype "passive"))
      (node (ref "R1") (pin "1") (pinfunction "1_1") (pintype "passive"))
      (node (ref "REG1117-3.3") (pin "1") (pinfunction "GND_1") (pintype "power_in"))
      (node (ref "RST") (pin "1") (pinfunction "1_1") (pintype "passive"))
      (node (ref "S1") (pin "6") (pinfunction "NO2_6") (pintype "passive"))
      (node (ref "U1") (pin "15") (pinfunction "GND_15") (pintype "power_in"))
    )
    (net (code "80") (name "Net-(DS1-K)") (class "Default")
      (node (ref "DS1") (pin "2") (pinfunction "K_2") (pintype "passive"))
      (node (ref "R1") (pin "2") (pinfunction "2_2") (pintype "passive"))
    )
    (net (code "81") (name "Net-(LED0-K)") (class "Default")
      (node (ref "LED0") (pin "2") (pinfunction "K_2") (pintype "passive"))
      (node (ref "R11") (pin "2") (pinfunction "2_2") (pintype "passive"))
    )
    (net (code "82") (name "Net-(LED1-K)") (class "Default")
      (node (ref "LED1") (pin "2") (pinfunction "K_2") (pintype "passive"))
      (node (ref "R12") (pin "2") (pinfunction "2_2") (pintype "passive"))
    )
    (net (code "83") (name "Net-(LED2-K)") (class "Default")
      (node (ref "LED2") (pin "2") (pinfunction "K_2") (pintype "passive"))
      (node (ref "R13") (pin "2") (pinfunction "2_2") (pintype "passive"))
    )
    (net (code "84") (name "Net-(LED3-K)") (class "Default")
      (node (ref "LED3") (pin "2") (pinfunction "K_2") (pintype "passive"))
      (node (ref "R14") (pin "2") (pinfunction "2_2") (pintype "passive"))
    )
    (net (code "85") (name "Net-(LED4-K)") (class "Default")
      (node (ref "LED4") (pin "2") (pinfunction "K_2") (pintype "passive"))
      (node (ref "R15") (pin "2") (pinfunction "2_2") (pintype "passive"))
    )
    (net (code "86") (name "Net-(LED5-K)") (class "Default")
      (node (ref "LED5") (pin "2") (pinfunction "K_2") (pintype "passive"))
      (node (ref "R16") (pin "2") (pinfunction "2_2") (pintype "passive"))
    )
    (net (code "87") (name "Net-(LED6-K)") (class "Default")
      (node (ref "LED6") (pin "2") (pinfunction "K_2") (pintype "passive"))
      (node (ref "R17") (pin "2") (pinfunction "2_2") (pintype "passive"))
    )
    (net (code "88") (name "Net-(LED7-K)") (class "Default")
      (node (ref "LED7") (pin "2") (pinfunction "K_2") (pintype "passive"))
      (node (ref "R18") (pin "2") (pinfunction "2_2") (pintype "passive"))
    )
    (net (code "89") (name "Net-(S1-COMMON1)") (class "Default")
      (node (ref "PROWER") (pin "1") (pinfunction "1_1") (pintype "passive"))
      (node (ref "S1") (pin "1") (pinfunction "COMMON1_1") (pintype "passive"))
      (node (ref "USB") (pin "1") (pinfunction "1_1") (pintype "passive"))
    )
    (net (code "90") (name "Net-(S1-COMMON2)") (class "Default")
      (node (ref "PROWER") (pin "2") (pinfunction "2_2") (pintype "passive"))
      (node (ref "S1") (pin "5") (pinfunction "COMMON2_5") (pintype "passive"))
      (node (ref "USB") (pin "4") (pinfunction "4_4") (pintype "passive"))
    )
    (net (code "91") (name "Net-(U1-C1+)") (class "Default")
      (node (ref "C5") (pin "1") (pinfunction "1_1") (pintype "passive"))
      (node (ref "U1") (pin "1") (pinfunction "C1+_1") (pintype "passive"))
    )
    (net (code "92") (name "Net-(U1-C1-)") (class "Default")
      (node (ref "C5") (pin "2") (pinfunction "2_2") (pintype "passive"))
      (node (ref "U1") (pin "3") (pinfunction "C1-_3") (pintype "passive"))
    )
    (net (code "93") (name "Net-(U1-C2+)") (class "Default")
      (node (ref "C6") (pin "1") (pinfunction "1_1") (pintype "passive"))
      (node (ref "U1") (pin "4") (pinfunction "C2+_4") (pintype "passive"))
    )
    (net (code "94") (name "Net-(U1-C2-)") (class "Default")
      (node (ref "C6") (pin "2") (pinfunction "2_2") (pintype "passive"))
      (node (ref "U1") (pin "5") (pinfunction "C2-_5") (pintype "passive"))
    )
    (net (code "95") (name "Net-(U1-R1IN)") (class "Default")
      (node (ref "COM2") (pin "3") (pinfunction "3_3") (pintype "passive"))
      (node (ref "U1") (pin "13") (pinfunction "R1IN_13") (pintype "input"))
    )
    (net (code "96") (name "Net-(U1-R2IN)") (class "Default")
      (node (ref "COM1") (pin "3") (pinfunction "3_3") (pintype "passive"))
      (node (ref "U1") (pin "8") (pinfunction "R2IN_8") (pintype "input"))
    )
    (net (code "97") (name "Net-(U1-T1OUT)") (class "Default")
      (node (ref "COM2") (pin "2") (pinfunction "2_2") (pintype "passive"))
      (node (ref "U1") (pin "14") (pinfunction "T1OUT_14") (pintype "output"))
    )
    (net (code "98") (name "Net-(U1-T2OUT)") (class "Default")
      (node (ref "COM1") (pin "2") (pinfunction "2_2") (pintype "passive"))
      (node (ref "U1") (pin "7") (pinfunction "T2OUT_7") (pintype "output"))
    )
    (net (code "99") (name "Net-(U1-VDD)") (class "Default")
      (node (ref "C7") (pin "1") (pinfunction "1_1") (pintype "passive"))
      (node (ref "U1") (pin "2") (pinfunction "VDD_2") (pintype "power_in"))
    )
    (net (code "100") (name "Net-(U1-VEE)") (class "Default")
      (node (ref "C9") (pin "2") (pinfunction "2_2") (pintype "passive"))
      (node (ref "U1") (pin "6") (pinfunction "VEE_6") (pintype "power_in"))
    )
    (net (code "101") (name "VCC") (class "Default")
      (node (ref "C10") (pin "1") (pinfunction "1_1") (pintype "passive"))
      (node (ref "C11") (pin "1") (pinfunction "1_1") (pintype "passive"))
      (node (ref "C3") (pin "1") (pinfunction "1_1") (pintype "passive"))
      (node (ref "C4") (pin "2") (pinfunction "2_2") (pintype "passive"))
      (node (ref "DS1") (pin "1") (pinfunction "A_1") (pintype "passive"))
      (node (ref "DownLoad") (pin "2") (pinfunction "2_2") (pintype "passive"))
      (node (ref "LED0") (pin "1") (pinfunction "A_1") (pintype "passive"))
      (node (ref "LED1") (pin "1") (pinfunction "A_1") (pintype "passive"))
      (node (ref "LED2") (pin "1") (pinfunction "A_1") (pintype "passive"))
      (node (ref "LED3") (pin "1") (pinfunction "A_1") (pintype "passive"))
      (node (ref "LED4") (pin "1") (pinfunction "A_1") (pintype "passive"))
      (node (ref "LED5") (pin "1") (pinfunction "A_1") (pintype "passive"))
      (node (ref "LED6") (pin "1") (pinfunction "A_1") (pintype "passive"))
      (node (ref "LED7") (pin "1") (pinfunction "A_1") (pintype "passive"))
      (node (ref "MSP430F149") (pin "1") (pinfunction "DVCC_1") (pintype "passive"))
      (node (ref "MSP430F149") (pin "64") (pinfunction "AVCC_64") (pintype "passive"))
      (node (ref "P1_16") (pin "1") (pinfunction "1_1") (pintype "passive"))
      (node (ref "P49_64") (pin "16") (pinfunction "16_16") (pintype "passive"))
      (node (ref "P7") (pin "4") (pinfunction "4_4") (pintype "passive"))
      (node (ref "P7") (pin "5") (pinfunction "5_5") (pintype "passive"))
      (node (ref "R2") (pin "1") (pinfunction "1_1") (pintype "passive"))
      (node (ref "REG1117-3.3") (pin "2") (pinfunction "OUT_2") (pintype "power_in"))
      (node (ref "REG1117-3.3") (pin "4") (pinfunction "OUT_4") (pintype "power_in"))
    )
    (net (code "102") (name "unconnected-(COM1-MH1-Pad10)") (class "Default")
      (node (ref "COM1") (pin "10") (pinfunction "MH1_10") (pintype "passive"))
    )
    (net (code "103") (name "unconnected-(COM1-MH2-Pad11)") (class "Default")
      (node (ref "COM1") (pin "11") (pinfunction "MH2_11") (pintype "passive"))
    )
    (net (code "104") (name "unconnected-(COM1-Pad1)") (class "Default")
      (node (ref "COM1") (pin "1") (pinfunction "1_1") (pintype "passive"))
    )
    (net (code "105") (name "unconnected-(COM1-Pad4)") (class "Default")
      (node (ref "COM1") (pin "4") (pinfunction "4_4") (pintype "passive"))
    )
    (net (code "106") (name "unconnected-(COM1-Pad5)") (class "Default")
      (node (ref "COM1") (pin "5") (pinfunction "5_5") (pintype "passive"))
    )
    (net (code "107") (name "unconnected-(COM1-Pad6)") (class "Default")
      (node (ref "COM1") (pin "6") (pinfunction "6_6") (pintype "passive"))
    )
    (net (code "108") (name "unconnected-(COM1-Pad7)") (class "Default")
      (node (ref "COM1") (pin "7") (pinfunction "7_7") (pintype "passive"))
    )
    (net (code "109") (name "unconnected-(COM1-Pad8)") (class "Default")
      (node (ref "COM1") (pin "8") (pinfunction "8_8") (pintype "passive"))
    )
    (net (code "110") (name "unconnected-(COM1-Pad9)") (class "Default")
      (node (ref "COM1") (pin "9") (pinfunction "9_9") (pintype "passive"))
    )
    (net (code "111") (name "unconnected-(COM2-MH1-Pad10)") (class "Default")
      (node (ref "COM2") (pin "10") (pinfunction "MH1_10") (pintype "passive"))
    )
    (net (code "112") (name "unconnected-(COM2-MH2-Pad11)") (class "Default")
      (node (ref "COM2") (pin "11") (pinfunction "MH2_11") (pintype "passive"))
    )
    (net (code "113") (name "unconnected-(COM2-Pad1)") (class "Default")
      (node (ref "COM2") (pin "1") (pinfunction "1_1") (pintype "passive"))
    )
    (net (code "114") (name "unconnected-(COM2-Pad4)") (class "Default")
      (node (ref "COM2") (pin "4") (pinfunction "4_4") (pintype "passive"))
    )
    (net (code "115") (name "unconnected-(COM2-Pad5)") (class "Default")
      (node (ref "COM2") (pin "5") (pinfunction "5_5") (pintype "passive"))
    )
    (net (code "116") (name "unconnected-(COM2-Pad6)") (class "Default")
      (node (ref "COM2") (pin "6") (pinfunction "6_6") (pintype "passive"))
    )
    (net (code "117") (name "unconnected-(COM2-Pad7)") (class "Default")
      (node (ref "COM2") (pin "7") (pinfunction "7_7") (pintype "passive"))
    )
    (net (code "118") (name "unconnected-(COM2-Pad8)") (class "Default")
      (node (ref "COM2") (pin "8") (pinfunction "8_8") (pintype "passive"))
    )
    (net (code "119") (name "unconnected-(COM2-Pad9)") (class "Default")
      (node (ref "COM2") (pin "9") (pinfunction "9_9") (pintype "passive"))
    )
    (net (code "120") (name "unconnected-(DownLoad-Pad4)") (class "Default")
      (node (ref "DownLoad") (pin "4") (pinfunction "4_4") (pintype "passive"))
    )
    (net (code "121") (name "unconnected-(DownLoad-Pad6)") (class "Default")
      (node (ref "DownLoad") (pin "6") (pinfunction "6_6") (pintype "passive"))
    )
    (net (code "122") (name "unconnected-(DownLoad-Pad8)") (class "Default")
      (node (ref "DownLoad") (pin "8") (pinfunction "8_8") (pintype "passive"))
    )
    (net (code "123") (name "unconnected-(DownLoad-Pad10)") (class "Default")
      (node (ref "DownLoad") (pin "10") (pinfunction "10_10") (pintype "passive"))
    )
    (net (code "124") (name "unconnected-(DownLoad-Pad12)") (class "Default")
      (node (ref "DownLoad") (pin "12") (pinfunction "12_12") (pintype "passive"))
    )
    (net (code "125") (name "unconnected-(DownLoad-Pad13)") (class "Default")
      (node (ref "DownLoad") (pin "13") (pinfunction "13_13") (pintype "passive"))
    )
    (net (code "126") (name "unconnected-(DownLoad-Pad14)") (class "Default")
      (node (ref "DownLoad") (pin "14") (pinfunction "14_14") (pintype "passive"))
    )
    (net (code "127") (name "unconnected-(S1-NC1-Pad2)") (class "Default")
      (node (ref "S1") (pin "2") (pinfunction "NC1_2") (pintype "passive"))
    )
    (net (code "128") (name "unconnected-(S1-NC2-Pad4)") (class "Default")
      (node (ref "S1") (pin "4") (pinfunction "NC2_4") (pintype "passive"))
    )
    (net (code "129") (name "unconnected-(USB-Pad2)") (class "Default")
      (node (ref "USB") (pin "2") (pinfunction "2_2") (pintype "passive"))
    )
    (net (code "130") (name "unconnected-(USB-Pad3)") (class "Default")
      (node (ref "USB") (pin "3") (pinfunction "3_3") (pintype "passive"))
    )
  )
)
